# audio-board.net
KiCad netlist of a schematic drawn in EAGLE
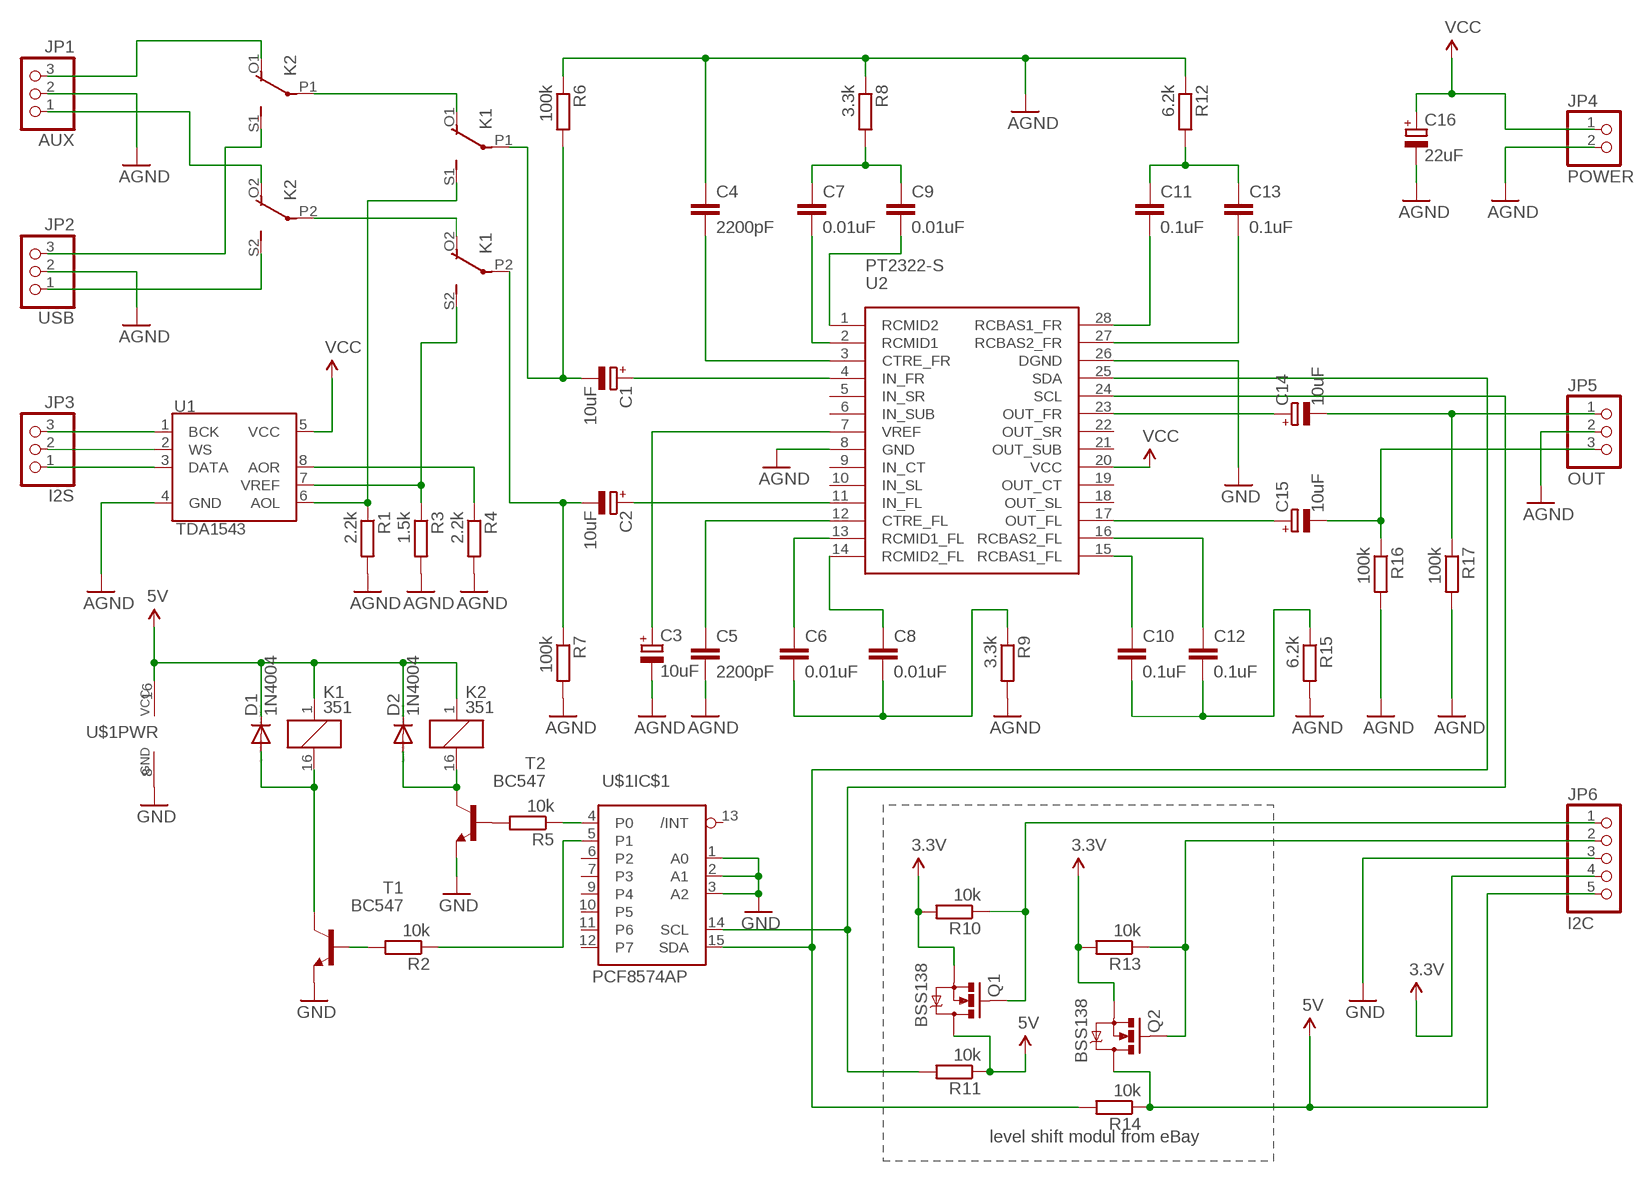
[diagram p0: schematic, sheet 1]

(export (version "E")
  (design (tool "Eeschema 10.0.6"))
  (components
    (comp (ref "AUX")
      (value "JP1")
      (footprint "eagle-import:1X03")
      (libsource (lib "eagle-import") (part "PINHD-1X3"))
    )
    (comp (ref "C1")
      (value "10uF")
      (footprint "eagle-import:E2-5")
      (libsource (lib "eagle-import") (part "CPOL-EUE2-5"))
    )
    (comp (ref "C2")
      (value "10uF")
      (footprint "eagle-import:E2-5")
      (libsource (lib "eagle-import") (part "CPOL-EUE2-5"))
    )
    (comp (ref "C3")
      (value "10uF")
      (footprint "eagle-import:E2-5")
      (libsource (lib "eagle-import") (part "CPOL-EUE2-5"))
    )
    (comp (ref "C4")
      (value "2200pF")
      (footprint "eagle-import:C025-025X050")
      (libsource (lib "eagle-import") (part "C-EU025-025X050"))
    )
    (comp (ref "C5")
      (value "2200pF")
      (footprint "eagle-import:C025-025X050")
      (libsource (lib "eagle-import") (part "C-EU025-025X050"))
    )
    (comp (ref "C6")
      (value "0.01uF")
      (footprint "eagle-import:C025-025X050")
      (libsource (lib "eagle-import") (part "C-EU025-025X050"))
    )
    (comp (ref "C7")
      (value "0.01uF")
      (footprint "eagle-import:C025-025X050")
      (libsource (lib "eagle-import") (part "C-EU025-025X050"))
    )
    (comp (ref "C8")
      (value "0.01uF")
      (footprint "eagle-import:C025-025X050")
      (libsource (lib "eagle-import") (part "C-EU025-025X050"))
    )
    (comp (ref "C9")
      (value "0.01uF")
      (footprint "eagle-import:C025-025X050")
      (libsource (lib "eagle-import") (part "C-EU025-025X050"))
    )
    (comp (ref "C10")
      (value "0.1uF")
      (footprint "eagle-import:C025-025X050")
      (libsource (lib "eagle-import") (part "C-EU025-025X050"))
    )
    (comp (ref "C11")
      (value "0.1uF")
      (footprint "eagle-import:C025-025X050")
      (libsource (lib "eagle-import") (part "C-EU025-025X050"))
    )
    (comp (ref "C12")
      (value "0.1uF")
      (footprint "eagle-import:C025-025X050")
      (libsource (lib "eagle-import") (part "C-EU025-025X050"))
    )
    (comp (ref "C13")
      (value "0.1uF")
      (footprint "eagle-import:C025-025X050")
      (libsource (lib "eagle-import") (part "C-EU025-025X050"))
    )
    (comp (ref "C14")
      (value "10uF")
      (footprint "eagle-import:E2-5")
      (libsource (lib "eagle-import") (part "CPOL-EUE2-5"))
    )
    (comp (ref "C15")
      (value "10uF")
      (footprint "eagle-import:E2-5")
      (libsource (lib "eagle-import") (part "CPOL-EUE2-5"))
    )
    (comp (ref "C16")
      (value "22uF")
      (footprint "eagle-import:E2,5-7")
      (libsource (lib "eagle-import") (part "CPOL-EUE2.5-7"))
    )
    (comp (ref "D1")
      (value "1N4004")
      (footprint "eagle-import:DO41-10")
      (libsource (lib "eagle-import") (part "1N4004"))
    )
    (comp (ref "D2")
      (value "1N4004")
      (footprint "eagle-import:DO41-10")
      (libsource (lib "eagle-import") (part "1N4004"))
    )
    (comp (ref "I2S")
      (value "JP3")
      (footprint "eagle-import:1X03")
      (libsource (lib "eagle-import") (part "PINHD-1X3"))
    )
    (comp (ref "JP4")
      (value "POWER")
      (footprint "eagle-import:1X02")
      (libsource (lib "eagle-import") (part "PINHD-1X2"))
    )
    (comp (ref "JP5")
      (value "OUT")
      (footprint "eagle-import:1X03")
      (libsource (lib "eagle-import") (part "PINHD-1X3"))
    )
    (comp (ref "JP6")
      (value "I2C")
      (footprint "eagle-import:1X05")
      (libsource (lib "eagle-import") (part "PINHD-1X5"))
    )
    (comp (ref "K1")
      (value "351")
      (footprint "eagle-import:351")
      (libsource (lib "eagle-import") (part "351"))
    )
    (comp (ref "K2")
      (value "351")
      (footprint "eagle-import:351")
      (libsource (lib "eagle-import") (part "351"))
    )
    (comp (ref "Q1")
      (value "BSS138")
      (footprint "eagle-import:SOT23-3")
      (libsource (lib "eagle-import") (part "MOSFET-NCHANNELSMD"))
    )
    (comp (ref "Q2")
      (value "BSS138")
      (footprint "eagle-import:SOT23-3")
      (libsource (lib "eagle-import") (part "MOSFET-NCHANNELSMD"))
    )
    (comp (ref "R1")
      (value "2.2k")
      (footprint "eagle-import:0207_10")
      (libsource (lib "eagle-import") (part "R-EU_0207/10"))
    )
    (comp (ref "R2")
      (value "10k")
      (footprint "eagle-import:0207_10")
      (libsource (lib "eagle-import") (part "R-EU_0207/10"))
    )
    (comp (ref "R3")
      (value "1.5k")
      (footprint "eagle-import:0207_10")
      (libsource (lib "eagle-import") (part "R-EU_0207/10"))
    )
    (comp (ref "R4")
      (value "2.2k")
      (footprint "eagle-import:0207_10")
      (libsource (lib "eagle-import") (part "R-EU_0207/10"))
    )
    (comp (ref "R5")
      (value "10k")
      (footprint "eagle-import:0207_10")
      (libsource (lib "eagle-import") (part "R-EU_0207/10"))
    )
    (comp (ref "R6")
      (value "100k")
      (footprint "eagle-import:0207_10")
      (libsource (lib "eagle-import") (part "R-EU_0207/10"))
    )
    (comp (ref "R7")
      (value "100k")
      (footprint "eagle-import:0207_10")
      (libsource (lib "eagle-import") (part "R-EU_0207/10"))
    )
    (comp (ref "R8")
      (value "3.3k")
      (footprint "eagle-import:0207_10")
      (libsource (lib "eagle-import") (part "R-EU_0207/10"))
    )
    (comp (ref "R9")
      (value "3.3k")
      (footprint "eagle-import:0207_10")
      (libsource (lib "eagle-import") (part "R-EU_0207/10"))
    )
    (comp (ref "R10")
      (value "10k")
      (footprint "eagle-import:0207_10")
      (libsource (lib "eagle-import") (part "R-EU_0207/10"))
    )
    (comp (ref "R11")
      (value "10k")
      (footprint "eagle-import:0207_10")
      (libsource (lib "eagle-import") (part "R-EU_0207/10"))
    )
    (comp (ref "R12")
      (value "6.2k")
      (footprint "eagle-import:0207_10")
      (libsource (lib "eagle-import") (part "R-EU_0207/10"))
    )
    (comp (ref "R13")
      (value "10k")
      (footprint "eagle-import:0207_10")
      (libsource (lib "eagle-import") (part "R-EU_0207/10"))
    )
    (comp (ref "R14")
      (value "10k")
      (footprint "eagle-import:0207_10")
      (libsource (lib "eagle-import") (part "R-EU_0207/10"))
    )
    (comp (ref "R15")
      (value "6.2k")
      (footprint "eagle-import:0207_10")
      (libsource (lib "eagle-import") (part "R-EU_0207/10"))
    )
    (comp (ref "R16")
      (value "100k")
      (footprint "eagle-import:0207_10")
      (libsource (lib "eagle-import") (part "R-EU_0207/10"))
    )
    (comp (ref "R17")
      (value "100k")
      (footprint "eagle-import:0207_10")
      (libsource (lib "eagle-import") (part "R-EU_0207/10"))
    )
    (comp (ref "T1")
      (value "BC547")
      (footprint "eagle-import:TO92")
      (libsource (lib "eagle-import") (part "BC547"))
    )
    (comp (ref "T2")
      (value "BC547")
      (footprint "eagle-import:TO92")
      (libsource (lib "eagle-import") (part "BC547"))
    )
    (comp (ref "U$1")
      (value "PCF8574AP")
      (footprint "eagle-import:DIL16")
      (libsource (lib "eagle-import") (part "PCF8574AP"))
    )
    (comp (ref "U1")
      (value "TDA1543")
      (footprint "eagle-import:DIL8")
      (libsource (lib "eagle-import") (part "TDA1543"))
    )
    (comp (ref "U2")
      (value "PT2322-S")
      (footprint "eagle-import:SOP28")
      (libsource (lib "eagle-import") (part "PT2322-S"))
    )
    (comp (ref "USB")
      (value "JP2")
      (footprint "eagle-import:1X03")
      (libsource (lib "eagle-import") (part "PINHD-1X3"))
    )
  )
  (nets
    (net (code "1") (name "3.3V") (class "Default")
      (node (ref "JP6") (pin "4") (pinfunction "4_4") (pintype "passive"))
      (node (ref "Q1") (pin "2") (pinfunction "S_2") (pintype "passive"))
      (node (ref "Q2") (pin "2") (pinfunction "S_2") (pintype "passive"))
      (node (ref "R10") (pin "2") (pinfunction "2_2") (pintype "passive"))
      (node (ref "R13") (pin "2") (pinfunction "2_2") (pintype "passive"))
    )
    (net (code "2") (name "5V") (class "Default")
      (node (ref "D1") (pin "C") (pinfunction "C_C") (pintype "passive"))
      (node (ref "D2") (pin "C") (pinfunction "C_C") (pintype "passive"))
      (node (ref "JP6") (pin "5") (pinfunction "5_5") (pintype "passive"))
      (node (ref "K1") (pin "1") (pinfunction "1_1") (pintype "passive"))
      (node (ref "K2") (pin "1") (pinfunction "1_1") (pintype "passive"))
      (node (ref "Q1") (pin "3") (pinfunction "D_3") (pintype "passive"))
      (node (ref "Q2") (pin "3") (pinfunction "D_3") (pintype "passive"))
      (node (ref "R11") (pin "1") (pinfunction "1_1") (pintype "passive"))
      (node (ref "R14") (pin "1") (pinfunction "1_1") (pintype "passive"))
      (node (ref "U$1") (pin "16") (pinfunction "VCC_16") (pintype "power_in"))
    )
    (net (code "3") (name "AGND") (class "Default")
      (node (ref "AUX") (pin "2") (pinfunction "2_2") (pintype "passive"))
      (node (ref "C16") (pin "-") (pinfunction "-_-") (pintype "passive"))
      (node (ref "C3") (pin "-") (pinfunction "-_-") (pintype "passive"))
      (node (ref "C4") (pin "1") (pinfunction "1_1") (pintype "passive"))
      (node (ref "C5") (pin "2") (pinfunction "2_2") (pintype "passive"))
      (node (ref "JP4") (pin "2") (pinfunction "2_2") (pintype "passive"))
      (node (ref "JP5") (pin "2") (pinfunction "2_2") (pintype "passive"))
      (node (ref "R1") (pin "2") (pinfunction "2_2") (pintype "passive"))
      (node (ref "R12") (pin "1") (pinfunction "1_1") (pintype "passive"))
      (node (ref "R15") (pin "2") (pinfunction "2_2") (pintype "passive"))
      (node (ref "R16") (pin "2") (pinfunction "2_2") (pintype "passive"))
      (node (ref "R17") (pin "2") (pinfunction "2_2") (pintype "passive"))
      (node (ref "R3") (pin "2") (pinfunction "2_2") (pintype "passive"))
      (node (ref "R4") (pin "2") (pinfunction "2_2") (pintype "passive"))
      (node (ref "R6") (pin "1") (pinfunction "1_1") (pintype "passive"))
      (node (ref "R7") (pin "2") (pinfunction "2_2") (pintype "passive"))
      (node (ref "R8") (pin "1") (pinfunction "1_1") (pintype "passive"))
      (node (ref "R9") (pin "2") (pinfunction "2_2") (pintype "passive"))
      (node (ref "U1") (pin "4") (pinfunction "GND_4") (pintype "bidirectional"))
      (node (ref "U2") (pin "8") (pinfunction "GND_8") (pintype "power_in"))
      (node (ref "USB") (pin "2") (pinfunction "2_2") (pintype "passive"))
    )
    (net (code "4") (name "GND") (class "Default")
      (node (ref "JP6") (pin "3") (pinfunction "3_3") (pintype "passive"))
      (node (ref "T1") (pin "1") (pinfunction "E_1") (pintype "passive"))
      (node (ref "T2") (pin "1") (pinfunction "E_1") (pintype "passive"))
      (node (ref "U$1") (pin "1") (pinfunction "A0_1") (pintype "input"))
      (node (ref "U$1") (pin "2") (pinfunction "A1_2") (pintype "input"))
      (node (ref "U$1") (pin "3") (pinfunction "A2_3") (pintype "input"))
      (node (ref "U$1") (pin "8") (pinfunction "GND_8") (pintype "power_in"))
      (node (ref "U2") (pin "26") (pinfunction "DGND_26") (pintype "power_in"))
    )
    (net (code "5") (name "Net-(C6-Pad2)") (class "Default")
      (node (ref "C6") (pin "2") (pinfunction "2_2") (pintype "passive"))
      (node (ref "C8") (pin "2") (pinfunction "2_2") (pintype "passive"))
      (node (ref "R9") (pin "1") (pinfunction "1_1") (pintype "passive"))
    )
    (net (code "6") (name "Net-(C7-Pad1)") (class "Default")
      (node (ref "C7") (pin "1") (pinfunction "1_1") (pintype "passive"))
      (node (ref "C9") (pin "1") (pinfunction "1_1") (pintype "passive"))
      (node (ref "R8") (pin "2") (pinfunction "2_2") (pintype "passive"))
    )
    (net (code "7") (name "Net-(C10-Pad2)") (class "Default")
      (node (ref "C10") (pin "2") (pinfunction "2_2") (pintype "passive"))
      (node (ref "C12") (pin "2") (pinfunction "2_2") (pintype "passive"))
      (node (ref "R15") (pin "1") (pinfunction "1_1") (pintype "passive"))
    )
    (net (code "8") (name "Net-(C11-Pad1)") (class "Default")
      (node (ref "C11") (pin "1") (pinfunction "1_1") (pintype "passive"))
      (node (ref "C13") (pin "1") (pinfunction "1_1") (pintype "passive"))
      (node (ref "R12") (pin "2") (pinfunction "2_2") (pintype "passive"))
    )
    (net (code "9") (name "Net-(C14-Pad-)") (class "Default")
      (node (ref "C14") (pin "-") (pinfunction "-_-") (pintype "passive"))
      (node (ref "JP5") (pin "1") (pinfunction "1_1") (pintype "passive"))
      (node (ref "R17") (pin "1") (pinfunction "1_1") (pintype "passive"))
    )
    (net (code "10") (name "Net-(C15-Pad-)") (class "Default")
      (node (ref "C15") (pin "-") (pinfunction "-_-") (pintype "passive"))
      (node (ref "JP5") (pin "3") (pinfunction "3_3") (pintype "passive"))
      (node (ref "R16") (pin "1") (pinfunction "1_1") (pintype "passive"))
    )
    (net (code "11") (name "Net-(K1A-2)") (class "Default")
      (node (ref "D1") (pin "A") (pinfunction "A_A") (pintype "passive"))
      (node (ref "K1") (pin "16") (pinfunction "2_16") (pintype "passive"))
      (node (ref "T1") (pin "3") (pinfunction "C_3") (pintype "passive"))
    )
    (net (code "12") (name "Net-(K1B-O)") (class "Default")
      (node (ref "K1") (pin "O1") (pinfunction "O_O1") (pintype "passive"))
      (node (ref "K2") (pin "P1") (pinfunction "P_P1") (pintype "passive"))
    )
    (net (code "13") (name "Net-(K1B-P)") (class "Default")
      (node (ref "C1") (pin "-") (pinfunction "-_-") (pintype "passive"))
      (node (ref "K1") (pin "P1") (pinfunction "P_P1") (pintype "passive"))
      (node (ref "R6") (pin "2") (pinfunction "2_2") (pintype "passive"))
    )
    (net (code "14") (name "Net-(K1B-S)") (class "Default")
      (node (ref "K1") (pin "S1") (pinfunction "S_S1") (pintype "passive"))
      (node (ref "R1") (pin "1") (pinfunction "1_1") (pintype "passive"))
      (node (ref "U1") (pin "6") (pinfunction "AOL_6") (pintype "bidirectional"))
    )
    (net (code "15") (name "Net-(K1C-O)") (class "Default")
      (node (ref "K1") (pin "O2") (pinfunction "O_O2") (pintype "passive"))
      (node (ref "K2") (pin "P2") (pinfunction "P_P2") (pintype "passive"))
    )
    (net (code "16") (name "Net-(K1C-P)") (class "Default")
      (node (ref "C2") (pin "-") (pinfunction "-_-") (pintype "passive"))
      (node (ref "K1") (pin "P2") (pinfunction "P_P2") (pintype "passive"))
      (node (ref "R7") (pin "1") (pinfunction "1_1") (pintype "passive"))
    )
    (net (code "17") (name "Net-(K1C-S)") (class "Default")
      (node (ref "K1") (pin "S2") (pinfunction "S_S2") (pintype "passive"))
      (node (ref "R3") (pin "1") (pinfunction "1_1") (pintype "passive"))
      (node (ref "U1") (pin "7") (pinfunction "VREF_7") (pintype "bidirectional"))
    )
    (net (code "18") (name "Net-(K2A-2)") (class "Default")
      (node (ref "D2") (pin "A") (pinfunction "A_A") (pintype "passive"))
      (node (ref "K2") (pin "16") (pinfunction "2_16") (pintype "passive"))
      (node (ref "T2") (pin "3") (pinfunction "C_3") (pintype "passive"))
    )
    (net (code "19") (name "Net-(K2B-O)") (class "Default")
      (node (ref "AUX") (pin "3") (pinfunction "3_3") (pintype "passive"))
      (node (ref "K2") (pin "O1") (pinfunction "O_O1") (pintype "passive"))
    )
    (net (code "20") (name "Net-(K2B-S)") (class "Default")
      (node (ref "K2") (pin "S1") (pinfunction "S_S1") (pintype "passive"))
      (node (ref "USB") (pin "3") (pinfunction "3_3") (pintype "passive"))
    )
    (net (code "21") (name "Net-(K2C-O)") (class "Default")
      (node (ref "AUX") (pin "1") (pinfunction "1_1") (pintype "passive"))
      (node (ref "K2") (pin "O2") (pinfunction "O_O2") (pintype "passive"))
    )
    (net (code "22") (name "Net-(K2C-S)") (class "Default")
      (node (ref "K2") (pin "S2") (pinfunction "S_S2") (pintype "passive"))
      (node (ref "USB") (pin "1") (pinfunction "1_1") (pintype "passive"))
    )
    (net (code "23") (name "Net-(Q1-G)") (class "Default")
      (node (ref "JP6") (pin "1") (pinfunction "1_1") (pintype "passive"))
      (node (ref "Q1") (pin "1") (pinfunction "G_1") (pintype "passive"))
      (node (ref "R10") (pin "1") (pinfunction "1_1") (pintype "passive"))
    )
    (net (code "24") (name "Net-(Q2-G)") (class "Default")
      (node (ref "JP6") (pin "2") (pinfunction "2_2") (pintype "passive"))
      (node (ref "Q2") (pin "1") (pinfunction "G_1") (pintype "passive"))
      (node (ref "R13") (pin "1") (pinfunction "1_1") (pintype "passive"))
    )
    (net (code "25") (name "Net-(T1-B)") (class "Default")
      (node (ref "R2") (pin "2") (pinfunction "2_2") (pintype "passive"))
      (node (ref "T1") (pin "2") (pinfunction "B_2") (pintype "passive"))
    )
    (net (code "26") (name "Net-(T2-B)") (class "Default")
      (node (ref "R5") (pin "2") (pinfunction "2_2") (pintype "passive"))
      (node (ref "T2") (pin "2") (pinfunction "B_2") (pintype "passive"))
    )
    (net (code "27") (name "Net-(U$1A-P0)") (class "Default")
      (node (ref "R5") (pin "1") (pinfunction "1_1") (pintype "passive"))
      (node (ref "U$1") (pin "4") (pinfunction "P0_4") (pintype "bidirectional"))
    )
    (net (code "28") (name "Net-(U$1A-P1)") (class "Default")
      (node (ref "R2") (pin "1") (pinfunction "1_1") (pintype "passive"))
      (node (ref "U$1") (pin "5") (pinfunction "P1_5") (pintype "bidirectional"))
    )
    (net (code "29") (name "Net-(U$1A-SCL)") (class "Default")
      (node (ref "R11") (pin "2") (pinfunction "2_2") (pintype "passive"))
      (node (ref "U$1") (pin "14") (pinfunction "SCL_14") (pintype "input"))
      (node (ref "U2") (pin "24") (pinfunction "SCL_24") (pintype "bidirectional"))
    )
    (net (code "30") (name "Net-(U$1A-SDA)") (class "Default")
      (node (ref "R14") (pin "2") (pinfunction "2_2") (pintype "passive"))
      (node (ref "U$1") (pin "15") (pinfunction "SDA_15") (pintype "bidirectional"))
      (node (ref "U2") (pin "25") (pinfunction "SDA_25") (pintype "bidirectional"))
    )
    (net (code "31") (name "Net-(U1-AOR)") (class "Default")
      (node (ref "R4") (pin "1") (pinfunction "1_1") (pintype "passive"))
      (node (ref "U1") (pin "8") (pinfunction "AOR_8") (pintype "bidirectional"))
    )
    (net (code "32") (name "Net-(U1-BCK)") (class "Default")
      (node (ref "I2S") (pin "3") (pinfunction "3_3") (pintype "passive"))
      (node (ref "U1") (pin "1") (pinfunction "BCK_1") (pintype "bidirectional"))
    )
    (net (code "33") (name "Net-(U1-DATA)") (class "Default")
      (node (ref "I2S") (pin "1") (pinfunction "1_1") (pintype "passive"))
      (node (ref "U1") (pin "3") (pinfunction "DATA_3") (pintype "bidirectional"))
    )
    (net (code "34") (name "Net-(U1-WS)") (class "Default")
      (node (ref "I2S") (pin "2") (pinfunction "2_2") (pintype "passive"))
      (node (ref "U1") (pin "2") (pinfunction "WS_2") (pintype "bidirectional"))
    )
    (net (code "35") (name "Net-(U2-CTRE_FL)") (class "Default")
      (node (ref "C5") (pin "1") (pinfunction "1_1") (pintype "passive"))
      (node (ref "U2") (pin "12") (pinfunction "CTRE_FL_12") (pintype "bidirectional"))
    )
    (net (code "36") (name "Net-(U2-CTRE_FR)") (class "Default")
      (node (ref "C4") (pin "2") (pinfunction "2_2") (pintype "passive"))
      (node (ref "U2") (pin "3") (pinfunction "CTRE_FR_3") (pintype "bidirectional"))
    )
    (net (code "37") (name "Net-(U2-IN_FL)") (class "Default")
      (node (ref "C2") (pin "+") (pinfunction "+_+") (pintype "passive"))
      (node (ref "U2") (pin "11") (pinfunction "IN_FL_11") (pintype "input"))
    )
    (net (code "38") (name "Net-(U2-IN_FR)") (class "Default")
      (node (ref "C1") (pin "+") (pinfunction "+_+") (pintype "passive"))
      (node (ref "U2") (pin "4") (pinfunction "IN_FR_4") (pintype "input"))
    )
    (net (code "39") (name "Net-(U2-OUT_FL)") (class "Default")
      (node (ref "C15") (pin "+") (pinfunction "+_+") (pintype "passive"))
      (node (ref "U2") (pin "17") (pinfunction "OUT_FL_17") (pintype "output"))
    )
    (net (code "40") (name "Net-(U2-OUT_FR)") (class "Default")
      (node (ref "C14") (pin "+") (pinfunction "+_+") (pintype "passive"))
      (node (ref "U2") (pin "23") (pinfunction "OUT_FR_23") (pintype "output"))
    )
    (net (code "41") (name "Net-(U2-RCBAS1_FL)") (class "Default")
      (node (ref "C10") (pin "1") (pinfunction "1_1") (pintype "passive"))
      (node (ref "U2") (pin "15") (pinfunction "RCBAS1_FL_15") (pintype "bidirectional"))
    )
    (net (code "42") (name "Net-(U2-RCBAS1_FR)") (class "Default")
      (node (ref "C11") (pin "2") (pinfunction "2_2") (pintype "passive"))
      (node (ref "U2") (pin "28") (pinfunction "RCBAS1_FR_28") (pintype "bidirectional"))
    )
    (net (code "43") (name "Net-(U2-RCBAS2_FL)") (class "Default")
      (node (ref "C12") (pin "1") (pinfunction "1_1") (pintype "passive"))
      (node (ref "U2") (pin "16") (pinfunction "RCBAS2_FL_16") (pintype "bidirectional"))
    )
    (net (code "44") (name "Net-(U2-RCBAS2_FR)") (class "Default")
      (node (ref "C13") (pin "2") (pinfunction "2_2") (pintype "passive"))
      (node (ref "U2") (pin "27") (pinfunction "RCBAS2_FR_27") (pintype "bidirectional"))
    )
    (net (code "45") (name "Net-(U2-RCMID1)") (class "Default")
      (node (ref "C7") (pin "2") (pinfunction "2_2") (pintype "passive"))
      (node (ref "U2") (pin "2") (pinfunction "RCMID1_2") (pintype "bidirectional"))
    )
    (net (code "46") (name "Net-(U2-RCMID1_FL)") (class "Default")
      (node (ref "C6") (pin "1") (pinfunction "1_1") (pintype "passive"))
      (node (ref "U2") (pin "13") (pinfunction "RCMID1_FL_13") (pintype "bidirectional"))
    )
    (net (code "47") (name "Net-(U2-RCMID2)") (class "Default")
      (node (ref "C9") (pin "2") (pinfunction "2_2") (pintype "passive"))
      (node (ref "U2") (pin "1") (pinfunction "RCMID2_1") (pintype "bidirectional"))
    )
    (net (code "48") (name "Net-(U2-RCMID2_FL)") (class "Default")
      (node (ref "C8") (pin "1") (pinfunction "1_1") (pintype "passive"))
      (node (ref "U2") (pin "14") (pinfunction "RCMID2_FL_14") (pintype "bidirectional"))
    )
    (net (code "49") (name "Net-(U2-VREF)") (class "Default")
      (node (ref "C3") (pin "+") (pinfunction "+_+") (pintype "passive"))
      (node (ref "U2") (pin "7") (pinfunction "VREF_7") (pintype "power_in"))
    )
    (net (code "50") (name "VCC") (class "Default")
      (node (ref "C16") (pin "+") (pinfunction "+_+") (pintype "passive"))
      (node (ref "JP4") (pin "1") (pinfunction "1_1") (pintype "passive"))
      (node (ref "U1") (pin "5") (pinfunction "VCC_5") (pintype "bidirectional"))
      (node (ref "U2") (pin "20") (pinfunction "VCC_20") (pintype "power_in"))
    )
    (net (code "51") (name "unconnected-(U$1A-P2-Pad6)") (class "Default")
      (node (ref "U$1") (pin "6") (pinfunction "P2_6") (pintype "bidirectional"))
    )
    (net (code "52") (name "unconnected-(U$1A-P3-Pad7)") (class "Default")
      (node (ref "U$1") (pin "7") (pinfunction "P3_7") (pintype "bidirectional"))
    )
    (net (code "53") (name "unconnected-(U$1A-P4-Pad9)") (class "Default")
      (node (ref "U$1") (pin "9") (pinfunction "P4_9") (pintype "bidirectional"))
    )
    (net (code "54") (name "unconnected-(U$1A-P5-Pad10)") (class "Default")
      (node (ref "U$1") (pin "10") (pinfunction "P5_10") (pintype "bidirectional"))
    )
    (net (code "55") (name "unconnected-(U$1A-P6-Pad11)") (class "Default")
      (node (ref "U$1") (pin "11") (pinfunction "P6_11") (pintype "bidirectional"))
    )
    (net (code "56") (name "unconnected-(U$1A-P7-Pad12)") (class "Default")
      (node (ref "U$1") (pin "12") (pinfunction "P7_12") (pintype "bidirectional"))
    )
    (net (code "57") (name "unconnected-(U$1A-{slash}INT-Pad13)") (class "Default")
      (node (ref "U$1") (pin "13") (pinfunction "/INT_13") (pintype "output"))
    )
    (net (code "58") (name "unconnected-(U2-IN_CT-Pad9)") (class "Default")
      (node (ref "U2") (pin "9") (pinfunction "IN_CT_9") (pintype "input"))
    )
    (net (code "59") (name "unconnected-(U2-IN_SL-Pad10)") (class "Default")
      (node (ref "U2") (pin "10") (pinfunction "IN_SL_10") (pintype "input"))
    )
    (net (code "60") (name "unconnected-(U2-IN_SR-Pad5)") (class "Default")
      (node (ref "U2") (pin "5") (pinfunction "IN_SR_5") (pintype "input"))
    )
    (net (code "61") (name "unconnected-(U2-IN_SUB-Pad6)") (class "Default")
      (node (ref "U2") (pin "6") (pinfunction "IN_SUB_6") (pintype "input"))
    )
    (net (code "62") (name "unconnected-(U2-OUT_CT-Pad19)") (class "Default")
      (node (ref "U2") (pin "19") (pinfunction "OUT_CT_19") (pintype "output"))
    )
    (net (code "63") (name "unconnected-(U2-OUT_SL-Pad18)") (class "Default")
      (node (ref "U2") (pin "18") (pinfunction "OUT_SL_18") (pintype "output"))
    )
    (net (code "64") (name "unconnected-(U2-OUT_SR-Pad22)") (class "Default")
      (node (ref "U2") (pin "22") (pinfunction "OUT_SR_22") (pintype "output"))
    )
    (net (code "65") (name "unconnected-(U2-OUT_SUB-Pad21)") (class "Default")
      (node (ref "U2") (pin "21") (pinfunction "OUT_SUB_21") (pintype "output"))
    )
  )
)
